# PicKit2Clone2.net
KiCad netlist of a schematic drawn in EAGLE
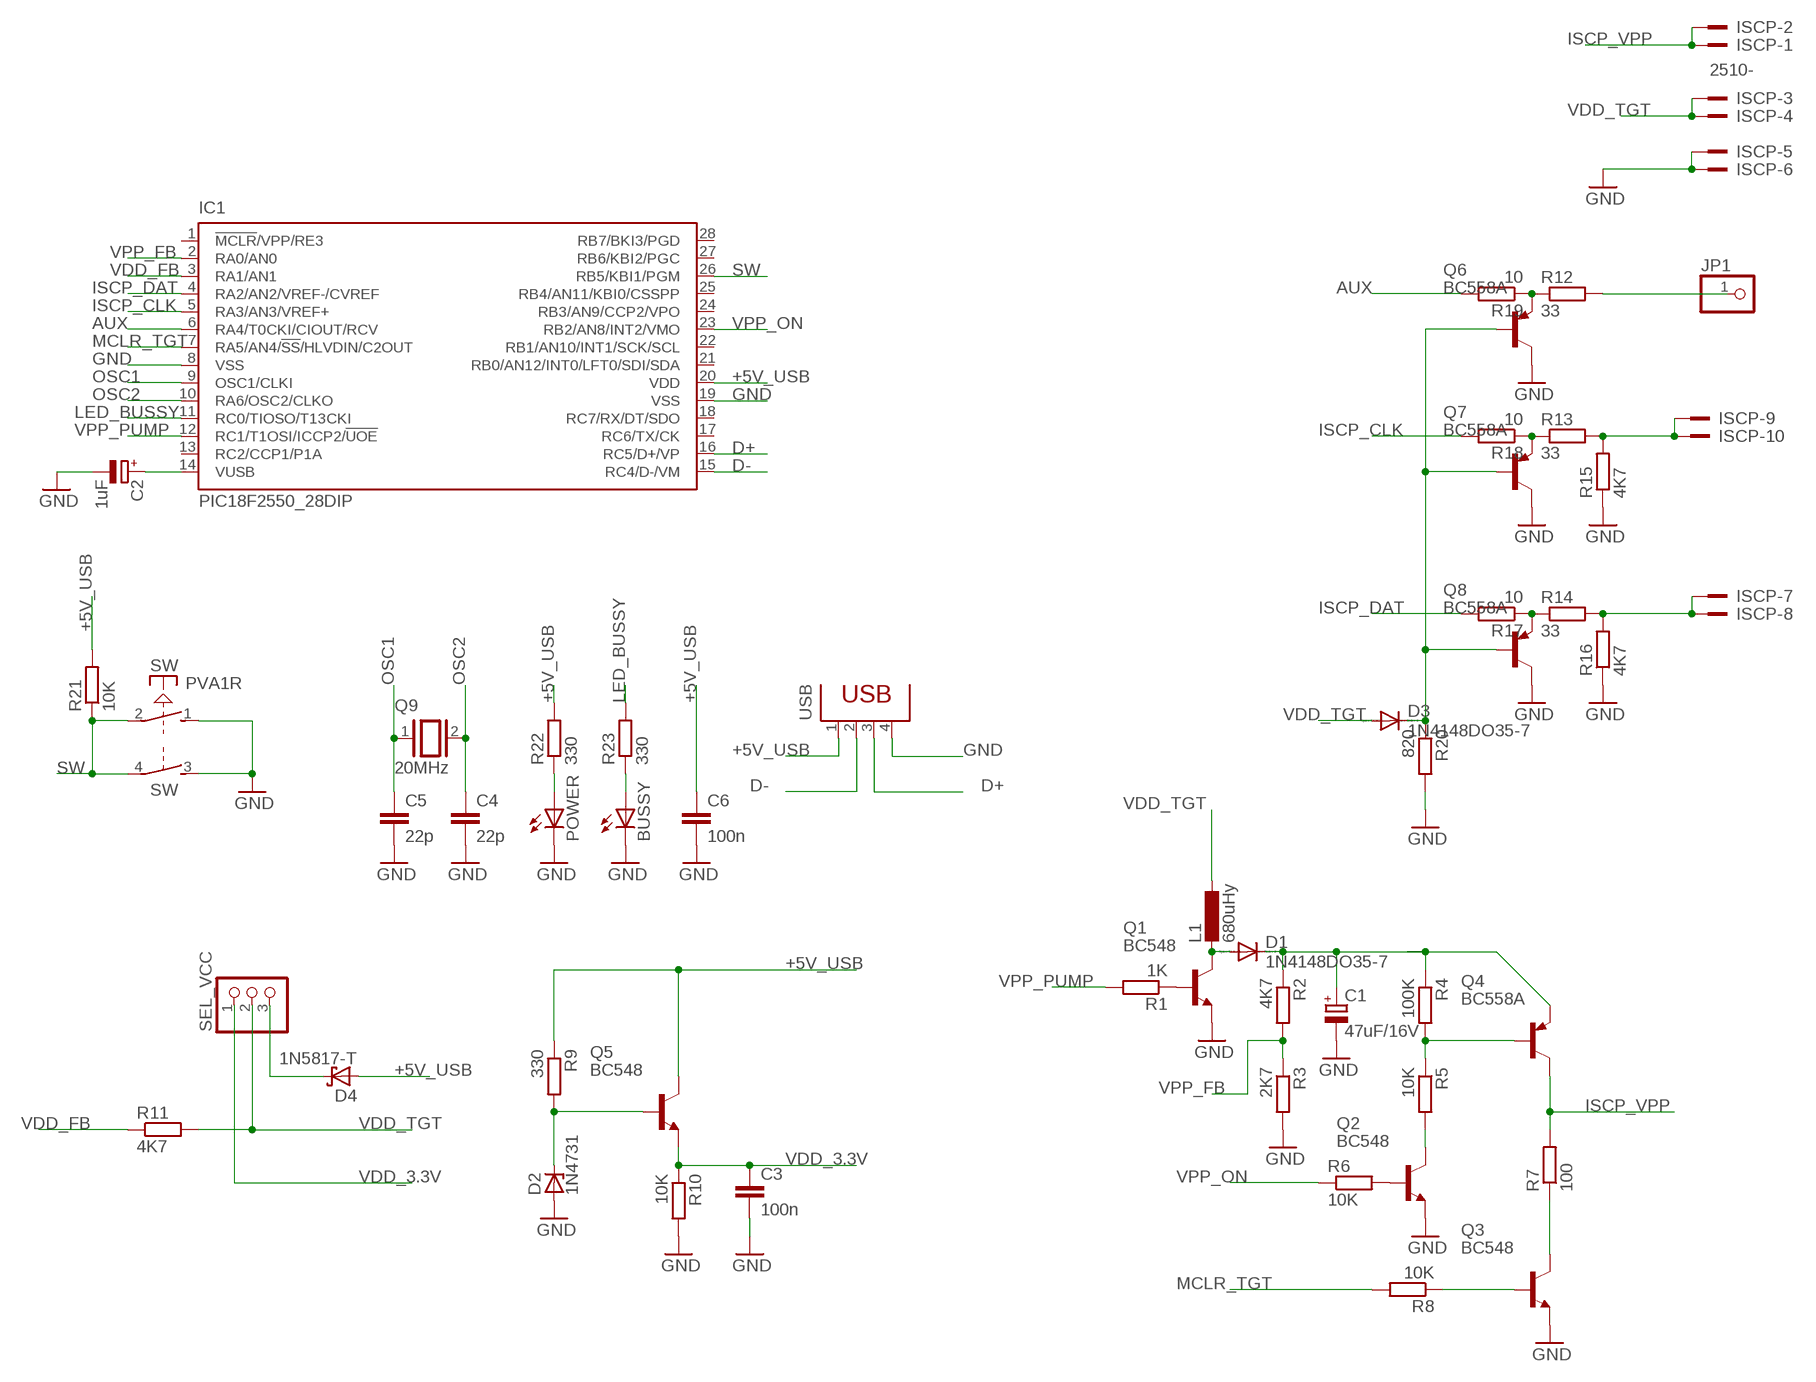
[diagram p0: schematic, sheet 1]

(export (version "E")
  (design (tool "Eeschema 10.0.6"))
  (components
    (comp (ref "BUSSY")
      (value "LED5MM")
      (footprint "eagle-import:LED5MM")
      (libsource (lib "eagle-import") (part "LED5MM"))
    )
    (comp (ref "C1")
      (value "47uF/16V")
      (footprint "eagle-import:E1,8-4")
      (libsource (lib "eagle-import") (part "CPOL-EUE1.8-4"))
    )
    (comp (ref "C2")
      (value "1uF")
      (footprint "eagle-import:E1,8-4")
      (libsource (lib "eagle-import") (part "CPOL-EUE1.8-4"))
    )
    (comp (ref "C3")
      (value "100n")
      (footprint "eagle-import:C025-025X050")
      (libsource (lib "eagle-import") (part "C-EU025-025X050"))
    )
    (comp (ref "C4")
      (value "22p")
      (footprint "eagle-import:C025-024X044")
      (libsource (lib "eagle-import") (part "C-EU025-024X044"))
    )
    (comp (ref "C5")
      (value "22p")
      (footprint "eagle-import:C025-024X044")
      (libsource (lib "eagle-import") (part "C-EU025-024X044"))
    )
    (comp (ref "C6")
      (value "100n")
      (footprint "eagle-import:C025-024X044")
      (libsource (lib "eagle-import") (part "C-EU025-024X044"))
    )
    (comp (ref "D1")
      (value "1N4148DO35-7")
      (footprint "eagle-import:DO35-7")
      (libsource (lib "eagle-import") (part "1N4148DO35-7"))
    )
    (comp (ref "D2")
      (value "1N4731")
      (footprint "eagle-import:DO41Z10")
      (libsource (lib "eagle-import") (part "ZENER-DIODEDO41Z10"))
    )
    (comp (ref "D3")
      (value "1N4148DO35-7")
      (footprint "eagle-import:DO35-7")
      (libsource (lib "eagle-import") (part "1N4148DO35-7"))
    )
    (comp (ref "D4")
      (value "1N5817-T")
      (footprint "eagle-import:DO41-7.6")
      (libsource (lib "eagle-import") (part "1N5817-T"))
    )
    (comp (ref "IC1")
      (value "PIC18F2550_28DIP")
      (footprint "eagle-import:DIL28-3")
      (fields (field (name "MF") "MICROCHIP") (field (name "MPN") "PIC18F2550-I/SP"))
      (libsource (lib "eagle-import") (part "PIC18F2_28DIP550"))
    )
    (comp (ref "ISCP")
      (value "2510-")
      (footprint "eagle-import:PAK100_2500-10")
      (fields (field (name "MF") "3M") (field (name "MPN") "2510-6002UB"))
      (libsource (lib "eagle-import") (part "2510-"))
    )
    (comp (ref "JP1")
      (value "PINHD-1X1")
      (footprint "eagle-import:1X01")
      (libsource (lib "eagle-import") (part "PINHD-1X1"))
    )
    (comp (ref "L1")
      (value "680uHy")
      (footprint "eagle-import:0204_5")
      (libsource (lib "eagle-import") (part "L-EU0204/5"))
    )
    (comp (ref "POWER")
      (value "LED5MM")
      (footprint "eagle-import:LED5MM")
      (libsource (lib "eagle-import") (part "LED5MM"))
    )
    (comp (ref "Q1")
      (value "BC548")
      (footprint "eagle-import:TO92-EBC")
      (libsource (lib "eagle-import") (part "BC548"))
    )
    (comp (ref "Q2")
      (value "BC548")
      (footprint "eagle-import:TO92-EBC")
      (libsource (lib "eagle-import") (part "BC548"))
    )
    (comp (ref "Q3")
      (value "BC548")
      (footprint "eagle-import:TO92-EBC")
      (libsource (lib "eagle-import") (part "BC548"))
    )
    (comp (ref "Q4")
      (value "BC558A")
      (footprint "eagle-import:TO92-EBC")
      (libsource (lib "eagle-import") (part "BC558A"))
    )
    (comp (ref "Q5")
      (value "BC548")
      (footprint "eagle-import:TO92-EBC")
      (libsource (lib "eagle-import") (part "BC548"))
    )
    (comp (ref "Q6")
      (value "BC558A")
      (footprint "eagle-import:TO92-EBC")
      (libsource (lib "eagle-import") (part "BC558A"))
    )
    (comp (ref "Q7")
      (value "BC558A")
      (footprint "eagle-import:TO92-EBC")
      (libsource (lib "eagle-import") (part "BC558A"))
    )
    (comp (ref "Q8")
      (value "BC558A")
      (footprint "eagle-import:TO92-EBC")
      (libsource (lib "eagle-import") (part "BC558A"))
    )
    (comp (ref "Q9")
      (value "20MHz")
      (footprint "eagle-import:QS")
      (libsource (lib "eagle-import") (part "XTAL/S"))
    )
    (comp (ref "R1")
      (value "1K")
      (footprint "eagle-import:0204_5")
      (libsource (lib "eagle-import") (part "R-EU_0204/5"))
    )
    (comp (ref "R2")
      (value "4K7")
      (footprint "eagle-import:0204_5")
      (libsource (lib "eagle-import") (part "R-EU_0204/5"))
    )
    (comp (ref "R3")
      (value "2K7")
      (footprint "eagle-import:0204_5")
      (libsource (lib "eagle-import") (part "R-EU_0204/5"))
    )
    (comp (ref "R4")
      (value "100K")
      (footprint "eagle-import:0204_5")
      (libsource (lib "eagle-import") (part "R-EU_0204/5"))
    )
    (comp (ref "R5")
      (value "10K")
      (footprint "eagle-import:0204_5")
      (libsource (lib "eagle-import") (part "R-EU_0204/5"))
    )
    (comp (ref "R6")
      (value "10K")
      (footprint "eagle-import:0204_7")
      (libsource (lib "eagle-import") (part "R-EU_0204/7"))
    )
    (comp (ref "R7")
      (value "100")
      (footprint "eagle-import:0204_5")
      (libsource (lib "eagle-import") (part "R-EU_0204/5"))
    )
    (comp (ref "R8")
      (value "10K")
      (footprint "eagle-import:0204_7")
      (libsource (lib "eagle-import") (part "R-EU_0204/7"))
    )
    (comp (ref "R9")
      (value "330")
      (footprint "eagle-import:0204_7")
      (libsource (lib "eagle-import") (part "R-EU_0204/7"))
    )
    (comp (ref "R10")
      (value "10K")
      (footprint "eagle-import:0204_5")
      (libsource (lib "eagle-import") (part "R-EU_0204/5"))
    )
    (comp (ref "R11")
      (value "4K7")
      (footprint "eagle-import:0204_5")
      (libsource (lib "eagle-import") (part "R-EU_0204/5"))
    )
    (comp (ref "R12")
      (value "33")
      (footprint "eagle-import:0204_5")
      (libsource (lib "eagle-import") (part "R-EU_0204/5"))
    )
    (comp (ref "R13")
      (value "33")
      (footprint "eagle-import:0204_5")
      (libsource (lib "eagle-import") (part "R-EU_0204/5"))
    )
    (comp (ref "R14")
      (value "33")
      (footprint "eagle-import:0204_7")
      (libsource (lib "eagle-import") (part "R-EU_0204/7"))
    )
    (comp (ref "R15")
      (value "4K7")
      (footprint "eagle-import:0204_5")
      (libsource (lib "eagle-import") (part "R-EU_0204/5"))
    )
    (comp (ref "R16")
      (value "4K7")
      (footprint "eagle-import:0204_7")
      (libsource (lib "eagle-import") (part "R-EU_0204/7"))
    )
    (comp (ref "R17")
      (value "10")
      (footprint "eagle-import:0204_5")
      (libsource (lib "eagle-import") (part "R-EU_0204/5"))
    )
    (comp (ref "R18")
      (value "10")
      (footprint "eagle-import:0204_5")
      (libsource (lib "eagle-import") (part "R-EU_0204/5"))
    )
    (comp (ref "R19")
      (value "10")
      (footprint "eagle-import:0204_5")
      (libsource (lib "eagle-import") (part "R-EU_0204/5"))
    )
    (comp (ref "R20")
      (value "820")
      (footprint "eagle-import:0204_5")
      (libsource (lib "eagle-import") (part "R-EU_0204/5"))
    )
    (comp (ref "R21")
      (value "10K")
      (footprint "eagle-import:0204_5")
      (libsource (lib "eagle-import") (part "R-EU_0204/5"))
    )
    (comp (ref "R22")
      (value "330")
      (footprint "eagle-import:0204_5")
      (libsource (lib "eagle-import") (part "R-EU_0204/5"))
    )
    (comp (ref "R23")
      (value "330")
      (footprint "eagle-import:0204_5")
      (libsource (lib "eagle-import") (part "R-EU_0204/5"))
    )
    (comp (ref "SEL_VCC")
      (value "PINHD-1X3")
      (footprint "eagle-import:1X03")
      (libsource (lib "eagle-import") (part "PINHD-1X3"))
    )
    (comp (ref "SW")
      (value "PVA1R")
      (footprint "eagle-import:PVA1R")
      (libsource (lib "eagle-import") (part "PVA1R"))
    )
    (comp (ref "USB")
      (value "PN61729")
      (footprint "eagle-import:PN61729")
      (libsource (lib "eagle-import") (part "PN61729"))
    )
  )
  (nets
    (net (code "1") (name "/+5V_USB") (class "Default")
      (node (ref "C6") (pin "1") (pinfunction "1_1") (pintype "passive"))
      (node (ref "D4") (pin "A") (pinfunction "A_A") (pintype "passive"))
      (node (ref "IC1") (pin "20") (pinfunction "VDD_20") (pintype "power_in"))
      (node (ref "Q5") (pin "C") (pinfunction "C_C") (pintype "passive"))
      (node (ref "R21") (pin "2") (pinfunction "2_2") (pintype "passive"))
      (node (ref "R22") (pin "2") (pinfunction "2_2") (pintype "passive"))
      (node (ref "R9") (pin "1") (pinfunction "1_1") (pintype "passive"))
      (node (ref "USB") (pin "1") (pinfunction "1_1") (pintype "passive"))
    )
    (net (code "2") (name "/AUX") (class "Default")
      (node (ref "IC1") (pin "6") (pinfunction "RA4/T0CKI/CIOUT/RCV_6") (pintype "bidirectional"))
      (node (ref "R19") (pin "2") (pinfunction "2_2") (pintype "passive"))
    )
    (net (code "3") (name "/D+") (class "Default")
      (node (ref "IC1") (pin "16") (pinfunction "RC5/D+/VP_16") (pintype "bidirectional"))
      (node (ref "USB") (pin "3") (pinfunction "3_3") (pintype "passive"))
    )
    (net (code "4") (name "/D-") (class "Default")
      (node (ref "IC1") (pin "15") (pinfunction "RC4/D-/VM_15") (pintype "bidirectional"))
      (node (ref "USB") (pin "2") (pinfunction "2_2") (pintype "passive"))
    )
    (net (code "5") (name "/ISCP_CLK") (class "Default")
      (node (ref "IC1") (pin "5") (pinfunction "RA3/AN3/VREF+_5") (pintype "bidirectional"))
      (node (ref "R18") (pin "2") (pinfunction "2_2") (pintype "passive"))
    )
    (net (code "6") (name "/ISCP_DAT") (class "Default")
      (node (ref "IC1") (pin "4") (pinfunction "RA2/AN2/VREF-/CVREF_4") (pintype "bidirectional"))
      (node (ref "R17") (pin "2") (pinfunction "2_2") (pintype "passive"))
    )
    (net (code "7") (name "/ISCP_VPP") (class "Default")
      (node (ref "ISCP") (pin "1") (pinfunction "KL_1") (pintype "passive"))
      (node (ref "ISCP") (pin "2") (pinfunction "KL_2") (pintype "passive"))
      (node (ref "Q4") (pin "C") (pinfunction "C_C") (pintype "passive"))
      (node (ref "R7") (pin "2") (pinfunction "2_2") (pintype "passive"))
    )
    (net (code "8") (name "/LED_BUSSY") (class "Default")
      (node (ref "IC1") (pin "11") (pinfunction "RC0/TIOSO/T13CKI_11") (pintype "bidirectional"))
      (node (ref "R23") (pin "2") (pinfunction "2_2") (pintype "passive"))
    )
    (net (code "9") (name "/MCLR_TGT") (class "Default")
      (node (ref "IC1") (pin "7") (pinfunction "RA5/AN4/~{SS}/HLVDIN/C2OUT_7") (pintype "bidirectional"))
      (node (ref "R8") (pin "2") (pinfunction "2_2") (pintype "passive"))
    )
    (net (code "10") (name "/OSC1") (class "Default")
      (node (ref "C5") (pin "1") (pinfunction "1_1") (pintype "passive"))
      (node (ref "IC1") (pin "9") (pinfunction "OSC1/CLKI_9") (pintype "input"))
      (node (ref "Q9") (pin "1") (pinfunction "1_1") (pintype "passive"))
    )
    (net (code "11") (name "/OSC2") (class "Default")
      (node (ref "C4") (pin "1") (pinfunction "1_1") (pintype "passive"))
      (node (ref "IC1") (pin "10") (pinfunction "RA6/OSC2/CLKO_10") (pintype "output"))
      (node (ref "Q9") (pin "2") (pinfunction "2_2") (pintype "passive"))
    )
    (net (code "12") (name "/SW") (class "Default")
      (node (ref "IC1") (pin "26") (pinfunction "RB5/KBI1/PGM_26") (pintype "bidirectional"))
      (node (ref "R21") (pin "1") (pinfunction "1_1") (pintype "passive"))
      (node (ref "SW") (pin "2") (pinfunction "P_2") (pintype "passive"))
      (node (ref "SW") (pin "4") (pinfunction "P_4") (pintype "passive"))
    )
    (net (code "13") (name "/VDD_3.3V") (class "Default")
      (node (ref "C3") (pin "1") (pinfunction "1_1") (pintype "passive"))
      (node (ref "Q5") (pin "E") (pinfunction "E_E") (pintype "passive"))
      (node (ref "R10") (pin "1") (pinfunction "1_1") (pintype "passive"))
      (node (ref "SEL_VCC") (pin "1") (pinfunction "1_1") (pintype "passive"))
    )
    (net (code "14") (name "/VDD_FB") (class "Default")
      (node (ref "IC1") (pin "3") (pinfunction "RA1/AN1_3") (pintype "bidirectional"))
      (node (ref "R11") (pin "1") (pinfunction "1_1") (pintype "passive"))
    )
    (net (code "15") (name "/VDD_TGT") (class "Default")
      (node (ref "D3") (pin "A") (pinfunction "A_A") (pintype "passive"))
      (node (ref "ISCP") (pin "3") (pinfunction "KL_3") (pintype "passive"))
      (node (ref "ISCP") (pin "4") (pinfunction "KL_4") (pintype "passive"))
      (node (ref "L1") (pin "1") (pinfunction "1_1") (pintype "passive"))
      (node (ref "R11") (pin "2") (pinfunction "2_2") (pintype "passive"))
      (node (ref "SEL_VCC") (pin "2") (pinfunction "2_2") (pintype "passive"))
    )
    (net (code "16") (name "/VPP_FB") (class "Default")
      (node (ref "IC1") (pin "2") (pinfunction "RA0/AN0_2") (pintype "bidirectional"))
      (node (ref "R2") (pin "2") (pinfunction "2_2") (pintype "passive"))
      (node (ref "R3") (pin "1") (pinfunction "1_1") (pintype "passive"))
    )
    (net (code "17") (name "/VPP_ON") (class "Default")
      (node (ref "IC1") (pin "23") (pinfunction "RB2/AN8/INT2/VMO_23") (pintype "bidirectional"))
      (node (ref "R6") (pin "1") (pinfunction "1_1") (pintype "passive"))
    )
    (net (code "18") (name "/VPP_PUMP") (class "Default")
      (node (ref "IC1") (pin "12") (pinfunction "RC1/T1OSI/ICCP2/~{UOE}_12") (pintype "bidirectional"))
      (node (ref "R1") (pin "2") (pinfunction "2_2") (pintype "passive"))
    )
    (net (code "19") (name "GND") (class "Default")
      (node (ref "BUSSY") (pin "K") (pinfunction "C_K") (pintype "passive"))
      (node (ref "C1") (pin "-") (pinfunction "-_-") (pintype "passive"))
      (node (ref "C2") (pin "-") (pinfunction "-_-") (pintype "passive"))
      (node (ref "C3") (pin "2") (pinfunction "2_2") (pintype "passive"))
      (node (ref "C4") (pin "2") (pinfunction "2_2") (pintype "passive"))
      (node (ref "C5") (pin "2") (pinfunction "2_2") (pintype "passive"))
      (node (ref "C6") (pin "2") (pinfunction "2_2") (pintype "passive"))
      (node (ref "D2") (pin "A") (pinfunction "A_A") (pintype "passive"))
      (node (ref "IC1") (pin "19") (pinfunction "VSS_19") (pintype "power_in"))
      (node (ref "IC1") (pin "8") (pinfunction "VSS_8") (pintype "power_in"))
      (node (ref "ISCP") (pin "5") (pinfunction "KL_5") (pintype "passive"))
      (node (ref "ISCP") (pin "6") (pinfunction "KL_6") (pintype "passive"))
      (node (ref "POWER") (pin "K") (pinfunction "C_K") (pintype "passive"))
      (node (ref "Q1") (pin "E") (pinfunction "E_E") (pintype "passive"))
      (node (ref "Q2") (pin "E") (pinfunction "E_E") (pintype "passive"))
      (node (ref "Q3") (pin "E") (pinfunction "E_E") (pintype "passive"))
      (node (ref "Q6") (pin "C") (pinfunction "C_C") (pintype "passive"))
      (node (ref "Q7") (pin "C") (pinfunction "C_C") (pintype "passive"))
      (node (ref "Q8") (pin "C") (pinfunction "C_C") (pintype "passive"))
      (node (ref "R10") (pin "2") (pinfunction "2_2") (pintype "passive"))
      (node (ref "R15") (pin "1") (pinfunction "1_1") (pintype "passive"))
      (node (ref "R16") (pin "1") (pinfunction "1_1") (pintype "passive"))
      (node (ref "R20") (pin "2") (pinfunction "2_2") (pintype "passive"))
      (node (ref "R3") (pin "2") (pinfunction "2_2") (pintype "passive"))
      (node (ref "SW") (pin "1") (pinfunction "S_1") (pintype "passive"))
      (node (ref "SW") (pin "3") (pinfunction "S_3") (pintype "passive"))
      (node (ref "USB") (pin "4") (pinfunction "4_4") (pintype "passive"))
    )
    (net (code "20") (name "Net-(BUSSY-PadA)") (class "Default")
      (node (ref "BUSSY") (pin "A") (pinfunction "A_A") (pintype "passive"))
      (node (ref "R23") (pin "1") (pinfunction "1_1") (pintype "passive"))
    )
    (net (code "21") (name "Net-(C1-Pad+)") (class "Default")
      (node (ref "C1") (pin "+") (pinfunction "+_+") (pintype "passive"))
      (node (ref "D1") (pin "C") (pinfunction "C_C") (pintype "passive"))
      (node (ref "Q4") (pin "E") (pinfunction "E_E") (pintype "passive"))
      (node (ref "R2") (pin "1") (pinfunction "1_1") (pintype "passive"))
      (node (ref "R4") (pin "1") (pinfunction "1_1") (pintype "passive"))
    )
    (net (code "22") (name "Net-(D1-PadA)") (class "Default")
      (node (ref "D1") (pin "A") (pinfunction "A_A") (pintype "passive"))
      (node (ref "L1") (pin "2") (pinfunction "2_2") (pintype "passive"))
      (node (ref "Q1") (pin "C") (pinfunction "C_C") (pintype "passive"))
    )
    (net (code "23") (name "Net-(D2-PadC)") (class "Default")
      (node (ref "D2") (pin "C") (pinfunction "C_C") (pintype "passive"))
      (node (ref "Q5") (pin "B") (pinfunction "B_B") (pintype "passive"))
      (node (ref "R9") (pin "2") (pinfunction "2_2") (pintype "passive"))
    )
    (net (code "24") (name "Net-(D3-PadC)") (class "Default")
      (node (ref "D3") (pin "C") (pinfunction "C_C") (pintype "passive"))
      (node (ref "Q6") (pin "B") (pinfunction "B_B") (pintype "passive"))
      (node (ref "Q7") (pin "B") (pinfunction "B_B") (pintype "passive"))
      (node (ref "Q8") (pin "B") (pinfunction "B_B") (pintype "passive"))
      (node (ref "R20") (pin "1") (pinfunction "1_1") (pintype "passive"))
    )
    (net (code "25") (name "Net-(D4-PadC)") (class "Default")
      (node (ref "D4") (pin "C") (pinfunction "C_C") (pintype "passive"))
      (node (ref "SEL_VCC") (pin "3") (pinfunction "3_3") (pintype "passive"))
    )
    (net (code "26") (name "Net-(IC1-VUSB)") (class "Default")
      (node (ref "C2") (pin "+") (pinfunction "+_+") (pintype "passive"))
      (node (ref "IC1") (pin "14") (pinfunction "VUSB_14") (pintype "bidirectional"))
    )
    (net (code "27") (name "Net-(ISCPB-KL)") (class "Default")
      (node (ref "ISCP") (pin "10") (pinfunction "KL_10") (pintype "passive"))
      (node (ref "ISCP") (pin "9") (pinfunction "KL_9") (pintype "passive"))
      (node (ref "R13") (pin "2") (pinfunction "2_2") (pintype "passive"))
      (node (ref "R15") (pin "2") (pinfunction "2_2") (pintype "passive"))
    )
    (net (code "28") (name "Net-(ISCPH-KL)") (class "Default")
      (node (ref "ISCP") (pin "7") (pinfunction "KL_7") (pintype "passive"))
      (node (ref "ISCP") (pin "8") (pinfunction "KL_8") (pintype "passive"))
      (node (ref "R14") (pin "2") (pinfunction "2_2") (pintype "passive"))
      (node (ref "R16") (pin "2") (pinfunction "2_2") (pintype "passive"))
    )
    (net (code "29") (name "Net-(JP1-Pad1)") (class "Default")
      (node (ref "JP1") (pin "1") (pinfunction "1_1") (pintype "passive"))
      (node (ref "R12") (pin "2") (pinfunction "2_2") (pintype "passive"))
    )
    (net (code "30") (name "Net-(POWER-PadA)") (class "Default")
      (node (ref "POWER") (pin "A") (pinfunction "A_A") (pintype "passive"))
      (node (ref "R22") (pin "1") (pinfunction "1_1") (pintype "passive"))
    )
    (net (code "31") (name "Net-(Q1-PadB)") (class "Default")
      (node (ref "Q1") (pin "B") (pinfunction "B_B") (pintype "passive"))
      (node (ref "R1") (pin "1") (pinfunction "1_1") (pintype "passive"))
    )
    (net (code "32") (name "Net-(Q2-PadB)") (class "Default")
      (node (ref "Q2") (pin "B") (pinfunction "B_B") (pintype "passive"))
      (node (ref "R6") (pin "2") (pinfunction "2_2") (pintype "passive"))
    )
    (net (code "33") (name "Net-(Q2-PadC)") (class "Default")
      (node (ref "Q2") (pin "C") (pinfunction "C_C") (pintype "passive"))
      (node (ref "R5") (pin "2") (pinfunction "2_2") (pintype "passive"))
    )
    (net (code "34") (name "Net-(Q3-PadB)") (class "Default")
      (node (ref "Q3") (pin "B") (pinfunction "B_B") (pintype "passive"))
      (node (ref "R8") (pin "1") (pinfunction "1_1") (pintype "passive"))
    )
    (net (code "35") (name "Net-(Q3-PadC)") (class "Default")
      (node (ref "Q3") (pin "C") (pinfunction "C_C") (pintype "passive"))
      (node (ref "R7") (pin "1") (pinfunction "1_1") (pintype "passive"))
    )
    (net (code "36") (name "Net-(Q4-PadB)") (class "Default")
      (node (ref "Q4") (pin "B") (pinfunction "B_B") (pintype "passive"))
      (node (ref "R4") (pin "2") (pinfunction "2_2") (pintype "passive"))
      (node (ref "R5") (pin "1") (pinfunction "1_1") (pintype "passive"))
    )
    (net (code "37") (name "Net-(Q6-PadE)") (class "Default")
      (node (ref "Q6") (pin "E") (pinfunction "E_E") (pintype "passive"))
      (node (ref "R12") (pin "1") (pinfunction "1_1") (pintype "passive"))
      (node (ref "R19") (pin "1") (pinfunction "1_1") (pintype "passive"))
    )
    (net (code "38") (name "Net-(Q7-PadE)") (class "Default")
      (node (ref "Q7") (pin "E") (pinfunction "E_E") (pintype "passive"))
      (node (ref "R13") (pin "1") (pinfunction "1_1") (pintype "passive"))
      (node (ref "R18") (pin "1") (pinfunction "1_1") (pintype "passive"))
    )
    (net (code "39") (name "Net-(Q8-PadE)") (class "Default")
      (node (ref "Q8") (pin "E") (pinfunction "E_E") (pintype "passive"))
      (node (ref "R14") (pin "1") (pinfunction "1_1") (pintype "passive"))
      (node (ref "R17") (pin "1") (pinfunction "1_1") (pintype "passive"))
    )
    (net (code "40") (name "unconnected-(IC1-RB0{slash}AN12{slash}INT0{slash}LFT0{slash}SDI{slash}SDA-Pad21)") (class "Default")
      (node (ref "IC1") (pin "21") (pinfunction "RB0/AN12/INT0/LFT0/SDI/SDA_21") (pintype "bidirectional"))
    )
    (net (code "41") (name "unconnected-(IC1-RB1{slash}AN10{slash}INT1{slash}SCK{slash}SCL-Pad22)") (class "Default")
      (node (ref "IC1") (pin "22") (pinfunction "RB1/AN10/INT1/SCK/SCL_22") (pintype "bidirectional"))
    )
    (net (code "42") (name "unconnected-(IC1-RB3{slash}AN9{slash}CCP2{slash}VPO-Pad24)") (class "Default")
      (node (ref "IC1") (pin "24") (pinfunction "RB3/AN9/CCP2/VPO_24") (pintype "bidirectional"))
    )
    (net (code "43") (name "unconnected-(IC1-RB4{slash}AN11{slash}KBI0{slash}CSSPP-Pad25)") (class "Default")
      (node (ref "IC1") (pin "25") (pinfunction "RB4/AN11/KBI0/CSSPP_25") (pintype "bidirectional"))
    )
    (net (code "44") (name "unconnected-(IC1-RB6{slash}KBI2{slash}PGC-Pad27)") (class "Default")
      (node (ref "IC1") (pin "27") (pinfunction "RB6/KBI2/PGC_27") (pintype "bidirectional"))
    )
    (net (code "45") (name "unconnected-(IC1-RB7{slash}BKI3{slash}PGD-Pad28)") (class "Default")
      (node (ref "IC1") (pin "28") (pinfunction "RB7/BKI3/PGD_28") (pintype "bidirectional"))
    )
    (net (code "46") (name "unconnected-(IC1-RC2{slash}CCP1{slash}P1A-Pad13)") (class "Default")
      (node (ref "IC1") (pin "13") (pinfunction "RC2/CCP1/P1A_13") (pintype "bidirectional"))
    )
    (net (code "47") (name "unconnected-(IC1-RC6{slash}TX{slash}CK-Pad17)") (class "Default")
      (node (ref "IC1") (pin "17") (pinfunction "RC6/TX/CK_17") (pintype "bidirectional"))
    )
    (net (code "48") (name "unconnected-(IC1-RC7{slash}RX{slash}DT{slash}SDO-Pad18)") (class "Default")
      (node (ref "IC1") (pin "18") (pinfunction "RC7/RX/DT/SDO_18") (pintype "bidirectional"))
    )
    (net (code "49") (name "unconnected-(IC1-~{MCLR}{slash}VPP{slash}RE3-Pad1)") (class "Default")
      (node (ref "IC1") (pin "1") (pinfunction "~{MCLR}/VPP/RE3_1") (pintype "input"))
    )
  )
)
